# Interface.net
KiCad netlist of a schematic drawn in Altium Designer
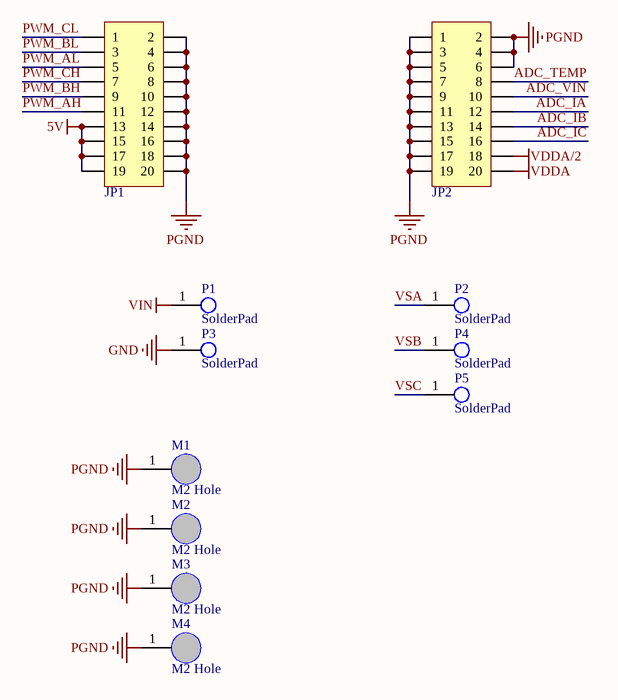
[diagram p0: Interface.SchDoc]

(export (version "E")
  (design (tool "Eeschema 10.0.6"))
  (components
    (comp (ref "JP1")
      (value "Header 2X10")
      (footprint "HDR2.0-LI-2x10P")
      (description "10*2P接插件")
      (libsource (lib "5.5 - 2.54mm(100mil)连接器(XH2.54)") (part "Header 10X2"))
    )
    (comp (ref "JP2")
      (value "Header 2X10")
      (footprint "HDR2.0-LI-2x10P")
      (description "10*2P接插件")
      (libsource (lib "5.5 - 2.54mm(100mil)连接器(XH2.54)") (part "Header 10X2"))
    )
    (comp (ref "M1") (value "M2 Hole") (footprint "M2 Hole") (libsource (lib "Driver") (part "M2_hole")))
    (comp (ref "M2") (value "M2 Hole") (footprint "M2 Hole") (libsource (lib "Driver") (part "M2_hole")))
    (comp (ref "M3") (value "M2 Hole") (footprint "M2 Hole") (libsource (lib "Driver") (part "M2_hole")))
    (comp (ref "M4") (value "M2 Hole") (footprint "M2 Hole") (libsource (lib "Driver") (part "M2_hole")))
    (comp (ref "P1")
      (value "SolderPad")
      (footprint "SolderPad")
      (description "焊盘")
      (libsource (lib "Driver") (part "SolderPad"))
    )
    (comp (ref "P2")
      (value "SolderPad")
      (footprint "SolderPad")
      (description "焊盘")
      (libsource (lib "Driver") (part "SolderPad"))
    )
    (comp (ref "P3")
      (value "SolderPad")
      (footprint "SolderPad")
      (description "焊盘")
      (libsource (lib "Driver") (part "SolderPad"))
    )
    (comp (ref "P4")
      (value "SolderPad")
      (footprint "SolderPad")
      (description "焊盘")
      (libsource (lib "Driver") (part "SolderPad"))
    )
    (comp (ref "P5")
      (value "SolderPad")
      (footprint "SolderPad")
      (description "焊盘")
      (libsource (lib "Driver") (part "SolderPad"))
    )
  )
  (nets
    (net (code "1") (name "/ADC_IA") (class "Default")
      (node (ref "JP2") (pin "12") (pinfunction "12_12") (pintype "passive"))
    )
    (net (code "2") (name "/ADC_IB") (class "Default")
      (node (ref "JP2") (pin "14") (pinfunction "14_14") (pintype "passive"))
    )
    (net (code "3") (name "/ADC_IC") (class "Default")
      (node (ref "JP2") (pin "16") (pinfunction "16_16") (pintype "passive"))
    )
    (net (code "4") (name "/ADC_TEMP") (class "Default")
      (node (ref "JP2") (pin "8") (pinfunction "8_8") (pintype "passive"))
    )
    (net (code "5") (name "/ADC_VIN") (class "Default")
      (node (ref "JP2") (pin "10") (pinfunction "10_10") (pintype "passive"))
    )
    (net (code "6") (name "/PWM_AH") (class "Default")
      (node (ref "JP1") (pin "11") (pinfunction "11_11") (pintype "passive"))
    )
    (net (code "7") (name "/PWM_AL") (class "Default")
      (node (ref "JP1") (pin "5") (pinfunction "5_5") (pintype "passive"))
    )
    (net (code "8") (name "/PWM_BH") (class "Default")
      (node (ref "JP1") (pin "9") (pinfunction "9_9") (pintype "passive"))
    )
    (net (code "9") (name "/PWM_BL") (class "Default")
      (node (ref "JP1") (pin "3") (pinfunction "3_3") (pintype "passive"))
    )
    (net (code "10") (name "/PWM_CH") (class "Default")
      (node (ref "JP1") (pin "7") (pinfunction "7_7") (pintype "passive"))
    )
    (net (code "11") (name "/PWM_CL") (class "Default")
      (node (ref "JP1") (pin "1") (pinfunction "1_1") (pintype "passive"))
    )
    (net (code "12") (name "/VSA") (class "Default")
      (node (ref "P2") (pin "1") (pinfunction "SolderPad_1") (pintype "passive"))
    )
    (net (code "13") (name "/VSB") (class "Default")
      (node (ref "P4") (pin "1") (pinfunction "SolderPad_1") (pintype "passive"))
    )
    (net (code "14") (name "/VSC") (class "Default")
      (node (ref "P5") (pin "1") (pinfunction "SolderPad_1") (pintype "passive"))
    )
    (net (code "15") (name "5V") (class "Default")
      (node (ref "JP1") (pin "13") (pinfunction "13_13") (pintype "passive"))
      (node (ref "JP1") (pin "15") (pinfunction "15_15") (pintype "passive"))
      (node (ref "JP1") (pin "17") (pinfunction "17_17") (pintype "passive"))
      (node (ref "JP1") (pin "19") (pinfunction "19_19") (pintype "passive"))
    )
    (net (code "16") (name "GND") (class "Default")
      (node (ref "P3") (pin "1") (pinfunction "SolderPad_1") (pintype "passive"))
    )
    (net (code "17") (name "PGND") (class "Default")
      (node (ref "JP1") (pin "10") (pinfunction "10_10") (pintype "passive"))
      (node (ref "JP1") (pin "12") (pinfunction "12_12") (pintype "passive"))
      (node (ref "JP1") (pin "14") (pinfunction "14_14") (pintype "passive"))
      (node (ref "JP1") (pin "16") (pinfunction "16_16") (pintype "passive"))
      (node (ref "JP1") (pin "18") (pinfunction "18_18") (pintype "passive"))
      (node (ref "JP1") (pin "2") (pinfunction "2_2") (pintype "passive"))
      (node (ref "JP1") (pin "20") (pinfunction "20_20") (pintype "passive"))
      (node (ref "JP1") (pin "4") (pinfunction "4_4") (pintype "passive"))
      (node (ref "JP1") (pin "6") (pinfunction "6_6") (pintype "passive"))
      (node (ref "JP1") (pin "8") (pinfunction "8_8") (pintype "passive"))
      (node (ref "JP2") (pin "1") (pinfunction "1_1") (pintype "passive"))
      (node (ref "JP2") (pin "11") (pinfunction "11_11") (pintype "passive"))
      (node (ref "JP2") (pin "13") (pinfunction "13_13") (pintype "passive"))
      (node (ref "JP2") (pin "15") (pinfunction "15_15") (pintype "passive"))
      (node (ref "JP2") (pin "17") (pinfunction "17_17") (pintype "passive"))
      (node (ref "JP2") (pin "19") (pinfunction "19_19") (pintype "passive"))
      (node (ref "JP2") (pin "2") (pinfunction "2_2") (pintype "passive"))
      (node (ref "JP2") (pin "3") (pinfunction "3_3") (pintype "passive"))
      (node (ref "JP2") (pin "4") (pinfunction "4_4") (pintype "passive"))
      (node (ref "JP2") (pin "5") (pinfunction "5_5") (pintype "passive"))
      (node (ref "JP2") (pin "6") (pinfunction "6_6") (pintype "passive"))
      (node (ref "JP2") (pin "7") (pinfunction "7_7") (pintype "passive"))
      (node (ref "JP2") (pin "9") (pinfunction "9_9") (pintype "passive"))
      (node (ref "M1") (pin "1") (pinfunction "Hole_1") (pintype "passive"))
      (node (ref "M2") (pin "1") (pinfunction "Hole_1") (pintype "passive"))
      (node (ref "M3") (pin "1") (pinfunction "Hole_1") (pintype "passive"))
      (node (ref "M4") (pin "1") (pinfunction "Hole_1") (pintype "passive"))
    )
    (net (code "18") (name "VDDA") (class "Default")
      (node (ref "JP2") (pin "20") (pinfunction "20_20") (pintype "passive"))
    )
    (net (code "19") (name "VDDA{slash}2") (class "Default")
      (node (ref "JP2") (pin "18") (pinfunction "18_18") (pintype "passive"))
    )
    (net (code "20") (name "VIN") (class "Default")
      (node (ref "P1") (pin "1") (pinfunction "SolderPad_1") (pintype "passive"))
    )
  )
)
